# Ethernet.net
KiCad netlist of a schematic drawn in Altium Designer
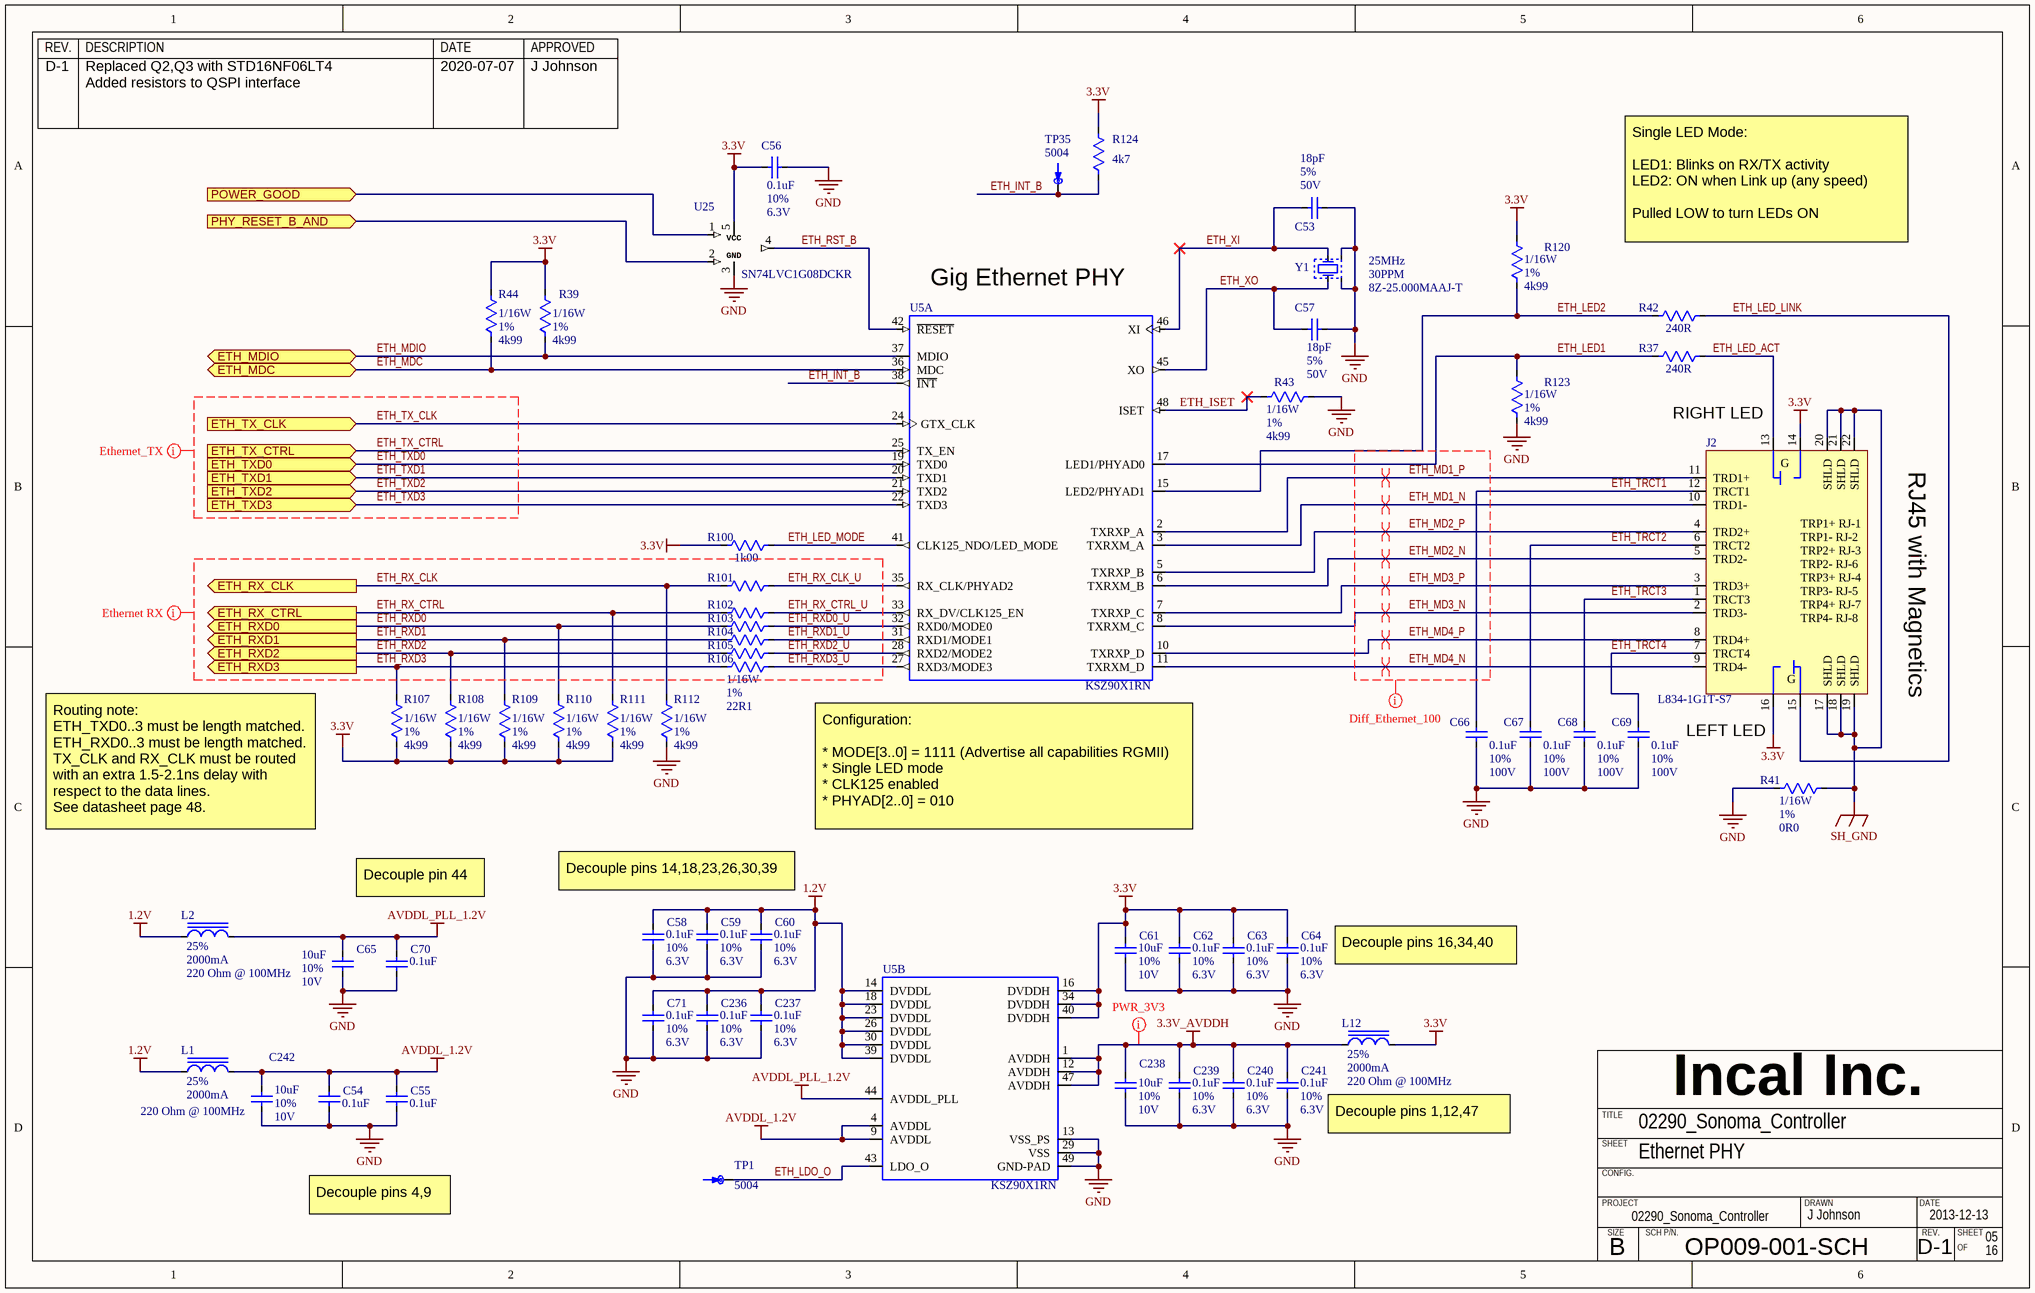
[diagram p0: Ethernet.SchDoc]

(export (version "E")
  (design (tool "Eeschema 10.0.6"))
  (components
    (comp (ref "C53")
      (value "18pF")
      (footprint "CAPC1005X33N")
      (description "Capacitor ceramic, C0G (NP0), 18pF, 50V, 5%, -55 to +125 C, EIA0402")
      (fields
        (field (name "TOLERANCE") "5%")
        (field (name "VOLTAGE") "50V")
        (field (name "Comment") "CAPACITOR_NP_TYPE1")
      )
      (libsource (lib "parts") (part "CAPACITOR_NP_TYPE1"))
    )
    (comp (ref "C54")
      (value "0.1uF")
      (footprint "CAPC0603X33N")
      (description "Capacitor ceramic, X5R, 0.1uF, 6.3V, 10%, -55 to +125 C, EIA0201")
      (fields (field (name "TOLERANCE") "10%") (field (name "VOLTAGE") "6.3V"))
      (libsource (lib "parts") (part "CAPACITOR_NP_TYPE1"))
    )
    (comp (ref "C55")
      (value "0.1uF")
      (footprint "CAPC0603X33N")
      (description "Capacitor ceramic, X5R, 0.1uF, 6.3V, 10%, -55 to +125 C, EIA0201")
      (fields (field (name "TOLERANCE") "10%") (field (name "VOLTAGE") "6.3V"))
      (libsource (lib "parts") (part "CAPACITOR_NP_TYPE1"))
    )
    (comp (ref "C56")
      (value "0.1uF")
      (footprint "CAPC0603X33N")
      (description "Capacitor ceramic, X5R, 0.1uF, 6.3V, 10%, -55 to +125 C, EIA0201")
      (fields
        (field (name "TOLERANCE") "10%")
        (field (name "VOLTAGE") "6.3V")
        (field (name "Comment") "CAPACITOR_NP_TYPE1")
      )
      (libsource (lib "parts") (part "CAPACITOR_NP_TYPE1"))
    )
    (comp (ref "C57")
      (value "18pF")
      (footprint "CAPC1005X33N")
      (description "Capacitor ceramic, C0G (NP0), 18pF, 50V, 5%, -55 to +125 C, EIA0402")
      (fields
        (field (name "TOLERANCE") "5%")
        (field (name "VOLTAGE") "50V")
        (field (name "Comment") "CAPACITOR_NP_TYPE1")
      )
      (libsource (lib "parts") (part "CAPACITOR_NP_TYPE1"))
    )
    (comp (ref "C58")
      (value "0.1uF")
      (footprint "CAPC0603X33N")
      (description "Capacitor ceramic, X5R, 0.1uF, 6.3V, 10%, -55 to +125 C, EIA0201")
      (fields
        (field (name "TOLERANCE") "10%")
        (field (name "VOLTAGE") "6.3V")
        (field (name "Comment") "CAPACITOR_NP_TYPE1")
      )
      (libsource (lib "parts") (part "CAPACITOR_NP_TYPE1"))
    )
    (comp (ref "C59")
      (value "0.1uF")
      (footprint "CAPC0603X33N")
      (description "Capacitor ceramic, X5R, 0.1uF, 6.3V, 10%, -55 to +125 C, EIA0201")
      (fields
        (field (name "TOLERANCE") "10%")
        (field (name "VOLTAGE") "6.3V")
        (field (name "Comment") "CAPACITOR_NP_TYPE1")
      )
      (libsource (lib "parts") (part "CAPACITOR_NP_TYPE1"))
    )
    (comp (ref "C60")
      (value "0.1uF")
      (footprint "CAPC0603X33N")
      (description "Capacitor ceramic, X5R, 0.1uF, 6.3V, 10%, -55 to +125 C, EIA0201")
      (fields
        (field (name "TOLERANCE") "10%")
        (field (name "VOLTAGE") "6.3V")
        (field (name "Comment") "CAPACITOR_NP_TYPE1")
      )
      (libsource (lib "parts") (part "CAPACITOR_NP_TYPE1"))
    )
    (comp (ref "C61")
      (value "10uF")
      (footprint "CAPC1608X38N")
      (description "Capacitor ceramic, X5R, 10uF, 10V, 10%, -55 to +85 C, EIA0603")
      (fields
        (field (name "TOLERANCE") "10%")
        (field (name "VOLTAGE") "10V")
        (field (name "Comment") "CAPACITOR_NP_TYPE1")
      )
      (libsource (lib "parts") (part "CAPACITOR_NP_TYPE1"))
    )
    (comp (ref "C62")
      (value "0.1uF")
      (footprint "CAPC0603X33N")
      (description "Capacitor ceramic, X5R, 0.1uF, 6.3V, 10%, -55 to +125 C, EIA0201")
      (fields
        (field (name "TOLERANCE") "10%")
        (field (name "VOLTAGE") "6.3V")
        (field (name "Comment") "CAPACITOR_NP_TYPE1")
      )
      (libsource (lib "parts") (part "CAPACITOR_NP_TYPE1"))
    )
    (comp (ref "C63")
      (value "0.1uF")
      (footprint "CAPC0603X33N")
      (description "Capacitor ceramic, X5R, 0.1uF, 6.3V, 10%, -55 to +125 C, EIA0201")
      (fields
        (field (name "TOLERANCE") "10%")
        (field (name "VOLTAGE") "6.3V")
        (field (name "Comment") "CAPACITOR_NP_TYPE1")
      )
      (libsource (lib "parts") (part "CAPACITOR_NP_TYPE1"))
    )
    (comp (ref "C64")
      (value "0.1uF")
      (footprint "CAPC0603X33N")
      (description "Capacitor ceramic, X5R, 0.1uF, 6.3V, 10%, -55 to +125 C, EIA0201")
      (fields
        (field (name "TOLERANCE") "10%")
        (field (name "VOLTAGE") "6.3V")
        (field (name "Comment") "CAPACITOR_NP_TYPE1")
      )
      (libsource (lib "parts") (part "CAPACITOR_NP_TYPE1"))
    )
    (comp (ref "C65")
      (value "10uF")
      (footprint "CAPC1608X38N")
      (description "Capacitor ceramic, X5R, 10uF, 10V, 10%, -55 to +85 C, EIA0603")
      (fields
        (field (name "TOLERANCE") "10%")
        (field (name "VOLTAGE") "10V")
        (field (name "Comment") "CAPACITOR_NP_TYPE1")
      )
      (libsource (lib "parts") (part "CAPACITOR_NP_TYPE1"))
    )
    (comp (ref "C66")
      (value "0.1uF")
      (footprint "CAPC1608X38N")
      (description "Capacitor ceramic, X7R, 0.1uF, 100V, 10%, -55 to +125 C, EIA0603")
      (fields
        (field (name "TOLERANCE") "10%")
        (field (name "VOLTAGE") "100V")
        (field (name "Comment") "CAPACITOR_NP_TYPE1")
      )
      (libsource (lib "parts") (part "CAPACITOR_NP_TYPE1"))
    )
    (comp (ref "C67")
      (value "0.1uF")
      (footprint "CAPC1608X38N")
      (description "Capacitor ceramic, X7R, 0.1uF, 100V, 10%, -55 to +125 C, EIA0603")
      (fields
        (field (name "TOLERANCE") "10%")
        (field (name "VOLTAGE") "100V")
        (field (name "Comment") "CAPACITOR_NP_TYPE1")
      )
      (libsource (lib "parts") (part "CAPACITOR_NP_TYPE1"))
    )
    (comp (ref "C68")
      (value "0.1uF")
      (footprint "CAPC1608X38N")
      (description "Capacitor ceramic, X7R, 0.1uF, 100V, 10%, -55 to +125 C, EIA0603")
      (fields
        (field (name "TOLERANCE") "10%")
        (field (name "VOLTAGE") "100V")
        (field (name "Comment") "CAPACITOR_NP_TYPE1")
      )
      (libsource (lib "parts") (part "CAPACITOR_NP_TYPE1"))
    )
    (comp (ref "C69")
      (value "0.1uF")
      (footprint "CAPC1608X38N")
      (description "Capacitor ceramic, X7R, 0.1uF, 100V, 10%, -55 to +125 C, EIA0603")
      (fields
        (field (name "TOLERANCE") "10%")
        (field (name "VOLTAGE") "100V")
        (field (name "Comment") "CAPACITOR_NP_TYPE1")
      )
      (libsource (lib "parts") (part "CAPACITOR_NP_TYPE1"))
    )
    (comp (ref "C70")
      (value "0.1uF")
      (footprint "CAPC0603X33N")
      (description "Capacitor ceramic, X5R, 0.1uF, 6.3V, 10%, -55 to +125 C, EIA0201")
      (fields (field (name "TOLERANCE") "10%") (field (name "VOLTAGE") "6.3V"))
      (libsource (lib "parts") (part "CAPACITOR_NP_TYPE1"))
    )
    (comp (ref "C71")
      (value "0.1uF")
      (footprint "CAPC0603X33N")
      (description "Capacitor ceramic, X5R, 0.1uF, 6.3V, 10%, -55 to +125 C, EIA0201")
      (fields
        (field (name "TOLERANCE") "10%")
        (field (name "VOLTAGE") "6.3V")
        (field (name "Comment") "CAPACITOR_NP_TYPE1")
      )
      (libsource (lib "parts") (part "CAPACITOR_NP_TYPE1"))
    )
    (comp (ref "C236")
      (value "0.1uF")
      (footprint "CAPC0603X33N")
      (description "Capacitor ceramic, X5R, 0.1uF, 6.3V, 10%, -55 to +125 C, EIA0201")
      (fields
        (field (name "TOLERANCE") "10%")
        (field (name "VOLTAGE") "6.3V")
        (field (name "Comment") "CAPACITOR_NP_TYPE1")
      )
      (libsource (lib "parts") (part "CAPACITOR_NP_TYPE1"))
    )
    (comp (ref "C237")
      (value "0.1uF")
      (footprint "CAPC0603X33N")
      (description "Capacitor ceramic, X5R, 0.1uF, 6.3V, 10%, -55 to +125 C, EIA0201")
      (fields
        (field (name "TOLERANCE") "10%")
        (field (name "VOLTAGE") "6.3V")
        (field (name "Comment") "CAPACITOR_NP_TYPE1")
      )
      (libsource (lib "parts") (part "CAPACITOR_NP_TYPE1"))
    )
    (comp (ref "C238")
      (value "10uF")
      (footprint "CAPC1608X38N")
      (description "Capacitor ceramic, X5R, 10uF, 10V, 10%, -55 to +85 C, EIA0603")
      (fields
        (field (name "TOLERANCE") "10%")
        (field (name "VOLTAGE") "10V")
        (field (name "Comment") "CAPACITOR_NP_TYPE1")
      )
      (libsource (lib "parts") (part "CAPACITOR_NP_TYPE1"))
    )
    (comp (ref "C239")
      (value "0.1uF")
      (footprint "CAPC0603X33N")
      (description "Capacitor ceramic, X5R, 0.1uF, 6.3V, 10%, -55 to +125 C, EIA0201")
      (fields
        (field (name "TOLERANCE") "10%")
        (field (name "VOLTAGE") "6.3V")
        (field (name "Comment") "CAPACITOR_NP_TYPE1")
      )
      (libsource (lib "parts") (part "CAPACITOR_NP_TYPE1"))
    )
    (comp (ref "C240")
      (value "0.1uF")
      (footprint "CAPC0603X33N")
      (description "Capacitor ceramic, X5R, 0.1uF, 6.3V, 10%, -55 to +125 C, EIA0201")
      (fields
        (field (name "TOLERANCE") "10%")
        (field (name "VOLTAGE") "6.3V")
        (field (name "Comment") "CAPACITOR_NP_TYPE1")
      )
      (libsource (lib "parts") (part "CAPACITOR_NP_TYPE1"))
    )
    (comp (ref "C241")
      (value "0.1uF")
      (footprint "CAPC0603X33N")
      (description "Capacitor ceramic, X5R, 0.1uF, 6.3V, 10%, -55 to +125 C, EIA0201")
      (fields
        (field (name "TOLERANCE") "10%")
        (field (name "VOLTAGE") "6.3V")
        (field (name "Comment") "CAPACITOR_NP_TYPE1")
      )
      (libsource (lib "parts") (part "CAPACITOR_NP_TYPE1"))
    )
    (comp (ref "C242")
      (value "10uF")
      (footprint "CAPC1608X38N")
      (description "Capacitor ceramic, X5R, 10uF, 10V, 10%, -55 to +85 C, EIA0603")
      (fields
        (field (name "TOLERANCE") "10%")
        (field (name "VOLTAGE") "10V")
        (field (name "Comment") "CAPACITOR_NP_TYPE1")
      )
      (libsource (lib "parts") (part "CAPACITOR_NP_TYPE1"))
    )
    (comp (ref "J2")
      (value "L834-1G1T-S7")
      (footprint "L834-1G1T-S7")
      (description "Connector RJ45, 10/100/1000, with Mag & 2 LED G/G, Tab down")
      (fields (field (name "Comment") "CON_RJ45_MAG_TYPE_9"))
      (libsource (lib "parts") (part "CON_RJ45_MAG_TYPE_9"))
    )
    (comp (ref "L1")
      (value "220 Ohm @ 100MHz")
      (footprint "INDC2012X85N")
      (description "Ferrite chip, 220 Ohm @ 100MHz, 2000mA, 25%, -55 to +125 C, 0805")
      (fields
        (field (name "TOLERANCE") "25%")
        (field (name "CURRENT") "2000mA")
        (field (name "Comment") "INDUCTOR_CORE_TYPE1")
      )
      (libsource (lib "parts") (part "INDUCTOR_CORE_TYPE1"))
    )
    (comp (ref "L2")
      (value "220 Ohm @ 100MHz")
      (footprint "INDC2012X85N")
      (description "Ferrite chip, 220 Ohm @ 100MHz, 2000mA, 25%, -55 to +125 C, 0805")
      (fields
        (field (name "TOLERANCE") "25%")
        (field (name "CURRENT") "2000mA")
        (field (name "Comment") "INDUCTOR_CORE_TYPE1")
      )
      (libsource (lib "parts") (part "INDUCTOR_CORE_TYPE1"))
    )
    (comp (ref "L12")
      (value "220 Ohm @ 100MHz")
      (footprint "INDC2012X85N")
      (description "Ferrite chip, 220 Ohm @ 100MHz, 2000mA, 25%, -55 to +125 C, 0805")
      (fields
        (field (name "TOLERANCE") "25%")
        (field (name "CURRENT") "2000mA")
        (field (name "Comment") "INDUCTOR_CORE_TYPE1")
      )
      (libsource (lib "parts") (part "INDUCTOR_CORE_TYPE1"))
    )
    (comp (ref "R37")
      (value "240R")
      (footprint "RESC1005X33N")
      (description "Resistor, 240R, 1/16W, 1%, -50 to +155 C, EIA0402, EIA(M)1005")
      (fields (field (name "VOLTAGE") "50V") (field (name "POWER") "1/16W"))
      (libsource (lib "parts") (part "RESISTOR_TYPE1"))
    )
    (comp (ref "R39")
      (value "4k99")
      (footprint "RESC1005X33N")
      (description "Resistor, 4k99, 1/16W, 1%, -50 to +155 C, EIA0402, EIA(M)1005")
      (fields (field (name "VOLTAGE") "50V") (field (name "POWER") "1/16W") (field (name "TOLERANCE") "1%"))
      (libsource (lib "parts") (part "RESISTOR_TYPE1"))
    )
    (comp (ref "R41")
      (value "0R0")
      (footprint "RESC1005X33N")
      (description "Resistor, 0R0, 1/16W, 1%, -50 to +155 C, EIA0402, EIA(M)1005")
      (fields (field (name "VOLTAGE") "50V") (field (name "POWER") "1/16W") (field (name "TOLERANCE") "1%"))
      (libsource (lib "parts") (part "RESISTOR_TYPE1"))
    )
    (comp (ref "R42")
      (value "240R")
      (footprint "RESC1005X33N")
      (description "Resistor, 240R, 1/16W, 1%, -50 to +155 C, EIA0402, EIA(M)1005")
      (fields (field (name "VOLTAGE") "50V") (field (name "POWER") "1/16W"))
      (libsource (lib "parts") (part "RESISTOR_TYPE1"))
    )
    (comp (ref "R43")
      (value "4k99")
      (footprint "RESC1005X33N")
      (description "Resistor, 4k99, 1/16W, 1%, -50 to +155 C, EIA0402, EIA(M)1005")
      (fields (field (name "VOLTAGE") "50V") (field (name "POWER") "1/16W") (field (name "TOLERANCE") "1%"))
      (libsource (lib "parts") (part "RESISTOR_TYPE1"))
    )
    (comp (ref "R44")
      (value "4k99")
      (footprint "RESC1005X33N")
      (description "Resistor, 4k99, 1/16W, 1%, -50 to +155 C, EIA0402, EIA(M)1005")
      (fields (field (name "VOLTAGE") "50V") (field (name "POWER") "1/16W") (field (name "TOLERANCE") "1%"))
      (libsource (lib "parts") (part "RESISTOR_TYPE1"))
    )
    (comp (ref "R100")
      (value "1k00")
      (footprint "RESC1005X33N")
      (description "Resistor, 1k00, 1/16W, 1%, -55 to +155 C, EIA0402")
      (fields (field (name "VOLTAGE") "50V") (field (name "POWER") "1/16W"))
      (libsource (lib "parts") (part "RESISTOR_TYPE1"))
    )
    (comp (ref "R101")
      (value "*")
      (footprint "RESC1005X33N")
      (description "Resistor, 22R1, 1/16W, 1%, -55 to +155 C, EIA0402")
      (fields (field (name "VOLTAGE") "50V") (field (name "POWER") "1/16W"))
      (libsource (lib "parts") (part "RESISTOR_TYPE1"))
    )
    (comp (ref "R102")
      (value "*")
      (footprint "RESC1005X33N")
      (description "Resistor, 22R1, 1/16W, 1%, -55 to +155 C, EIA0402")
      (fields (field (name "VOLTAGE") "50V") (field (name "POWER") "1/16W"))
      (libsource (lib "parts") (part "RESISTOR_TYPE1"))
    )
    (comp (ref "R103")
      (value "*")
      (footprint "RESC1005X33N")
      (description "Resistor, 22R1, 1/16W, 1%, -55 to +155 C, EIA0402")
      (fields (field (name "VOLTAGE") "50V") (field (name "POWER") "1/16W"))
      (libsource (lib "parts") (part "RESISTOR_TYPE1"))
    )
    (comp (ref "R104")
      (value "*")
      (footprint "RESC1005X33N")
      (description "Resistor, 22R1, 1/16W, 1%, -55 to +155 C, EIA0402")
      (fields (field (name "VOLTAGE") "50V") (field (name "POWER") "1/16W"))
      (libsource (lib "parts") (part "RESISTOR_TYPE1"))
    )
    (comp (ref "R105")
      (value "*")
      (footprint "RESC1005X33N")
      (description "Resistor, 22R1, 1/16W, 1%, -55 to +155 C, EIA0402")
      (fields (field (name "VOLTAGE") "50V") (field (name "POWER") "1/16W"))
      (libsource (lib "parts") (part "RESISTOR_TYPE1"))
    )
    (comp (ref "R106")
      (value "22R1")
      (footprint "RESC1005X33N")
      (description "Resistor, 22R1, 1/16W, 1%, -55 to +155 C, EIA0402")
      (fields (field (name "VOLTAGE") "50V") (field (name "POWER") "1/16W") (field (name "TOLERANCE") "1%"))
      (libsource (lib "parts") (part "RESISTOR_TYPE1"))
    )
    (comp (ref "R107")
      (value "4k99")
      (footprint "RESC1005X33N")
      (description "Resistor, 4k99, 1/16W, 1%, -50 to +155 C, EIA0402, EIA(M)1005")
      (fields (field (name "VOLTAGE") "50V") (field (name "POWER") "1/16W") (field (name "TOLERANCE") "1%"))
      (libsource (lib "parts") (part "RESISTOR_TYPE1"))
    )
    (comp (ref "R108")
      (value "4k99")
      (footprint "RESC1005X33N")
      (description "Resistor, 4k99, 1/16W, 1%, -50 to +155 C, EIA0402, EIA(M)1005")
      (fields (field (name "VOLTAGE") "50V") (field (name "POWER") "1/16W") (field (name "TOLERANCE") "1%"))
      (libsource (lib "parts") (part "RESISTOR_TYPE1"))
    )
    (comp (ref "R109")
      (value "4k99")
      (footprint "RESC1005X33N")
      (description "Resistor, 4k99, 1/16W, 1%, -50 to +155 C, EIA0402, EIA(M)1005")
      (fields (field (name "VOLTAGE") "50V") (field (name "POWER") "1/16W") (field (name "TOLERANCE") "1%"))
      (libsource (lib "parts") (part "RESISTOR_TYPE1"))
    )
    (comp (ref "R110")
      (value "4k99")
      (footprint "RESC1005X33N")
      (description "Resistor, 4k99, 1/16W, 1%, -50 to +155 C, EIA0402, EIA(M)1005")
      (fields (field (name "VOLTAGE") "50V") (field (name "POWER") "1/16W") (field (name "TOLERANCE") "1%"))
      (libsource (lib "parts") (part "RESISTOR_TYPE1"))
    )
    (comp (ref "R111")
      (value "4k99")
      (footprint "RESC1005X33N")
      (description "Resistor, 4k99, 1/16W, 1%, -50 to +155 C, EIA0402, EIA(M)1005")
      (fields (field (name "VOLTAGE") "50V") (field (name "POWER") "1/16W") (field (name "TOLERANCE") "1%"))
      (libsource (lib "parts") (part "RESISTOR_TYPE1"))
    )
    (comp (ref "R112")
      (value "4k99")
      (footprint "RESC1005X33N")
      (description "Resistor, 4k99, 1/16W, 1%, -50 to +155 C, EIA0402, EIA(M)1005")
      (fields (field (name "VOLTAGE") "50V") (field (name "POWER") "1/16W") (field (name "TOLERANCE") "1%"))
      (libsource (lib "parts") (part "RESISTOR_TYPE1"))
    )
    (comp (ref "R120")
      (value "4k99")
      (footprint "RESC1005X33N")
      (description "Resistor, 4k99, 1/16W, 1%, -50 to +155 C, EIA0402, EIA(M)1005")
      (fields (field (name "VOLTAGE") "50V") (field (name "POWER") "1/16W") (field (name "TOLERANCE") "1%"))
      (libsource (lib "parts") (part "RESISTOR_TYPE1"))
    )
    (comp (ref "R123")
      (value "4k99")
      (footprint "RESC1005X33N")
      (description "Resistor, 4k99, 1/16W, 1%, -50 to +155 C, EIA0402, EIA(M)1005")
      (fields (field (name "VOLTAGE") "50V") (field (name "POWER") "1/16W") (field (name "TOLERANCE") "1%"))
      (libsource (lib "parts") (part "RESISTOR_TYPE1"))
    )
    (comp (ref "R124")
      (value "4k7")
      (footprint "RESC1005X33N")
      (description "Resistor, 4k7, 1/16W, 1%, -55 to +155 C, EIA0402")
      (fields (field (name "VOLTAGE") "50V") (field (name "POWER") "1/16W"))
      (libsource (lib "parts") (part "RESISTOR_TYPE1"))
    )
    (comp (ref "TP1")
      (value "5004")
      (footprint "KEY_5004")
      (description "Test point bead, yellow, Keystone Electronics, Thru-hole,")
      (fields (field (name "POWER") "Pow") (field (name "VOLTAGE") "Vol"))
      (libsource (lib "") (part "TEST_POINT_TYPE4_1"))
    )
    (comp (ref "TP35")
      (value "5004")
      (footprint "KEY_5004")
      (description "Test point bead, yellow, Keystone Electronics, Thru-hole,")
      (fields (field (name "POWER") "Pow") (field (name "VOLTAGE") "Vol"))
      (libsource (lib "parts") (part "TEST_POINT_TYPE4"))
    )
    (comp (ref "U5")
      (value "KSZ90X1RN")
      (footprint "QFN50P700X700X90-49N")
      (description "10/100/1000 ethernet PHY with RGMII, 3.3V,1.2V, 0, -40 to +85 C, 0, QFN48")
      (fields (field (name "POWER") "0") (field (name "VOLTAGE") "3.3V,1.2V"))
      (libsource (lib "parts") (part "KSZ90X1RN"))
    )
    (comp (ref "U25")
      (value "SN74LVC1G08DCKR")
      (footprint "SOT65P210X110-5N")
      (description "Single 2-input AND gate, 1.65V to 5.5V")
      (fields (field (name "POWER") "Pow") (field (name "VOLTAGE") "1.65V to 5.5V"))
      (libsource (lib "parts") (part "SN74LVC1G08"))
    )
    (comp (ref "Y1")
      (value "25MHz")
      (footprint "OSCSC185P200X250X55-4N")
      (description "Crystal, 25MHz, 30ppm, 100uW, -40 to +85 C, SMT")
      (fields
        (field (name "POWER") "100uW")
        (field (name "TOLERANCE") "30PPM")
        (field (name "MFG PART NUMBER 1") "8Z-25.000MAAJ-T")
      )
      (libsource (lib "parts") (part "XTAL_TYPE3"))
    )
  )
  (nets
    (net (code "1") (name "/ETH_INT_B") (class "Default")
      (node (ref "R124") (pin "2") (pinfunction "2_2") (pintype "passive"))
      (node (ref "TP35") (pin "1") (pinfunction "1_1") (pintype "passive"))
      (node (ref "U5") (pin "38") (pinfunction "~{INT}_38") (pintype "output"))
    )
    (net (code "2") (name "/ETH_ISET") (class "Default")
      (node (ref "R43") (pin "2") (pinfunction "2_2") (pintype "passive"))
      (node (ref "U5") (pin "48") (pinfunction "ISET_48") (pintype "input"))
    )
    (net (code "3") (name "/ETH_LDO_O") (class "Default")
      (node (ref "TP1") (pin "1") (pinfunction "1_1") (pintype "passive"))
      (node (ref "U5") (pin "43") (pinfunction "LDO_O_43") (pintype "power_in"))
    )
    (net (code "4") (name "/ETH_LED1") (class "Default")
      (node (ref "R123") (pin "2") (pinfunction "2_2") (pintype "passive"))
      (node (ref "R37") (pin "1") (pinfunction "1_1") (pintype "passive"))
      (node (ref "U5") (pin "17") (pinfunction "LED1/PHYAD0_17") (pintype "bidirectional"))
    )
    (net (code "5") (name "/ETH_LED2") (class "Default")
      (node (ref "R120") (pin "1") (pinfunction "1_1") (pintype "passive"))
      (node (ref "R42") (pin "1") (pinfunction "1_1") (pintype "passive"))
      (node (ref "U5") (pin "15") (pinfunction "LED2/PHYAD1_15") (pintype "bidirectional"))
    )
    (net (code "6") (name "/ETH_LED_ACT") (class "Default")
      (node (ref "J2") (pin "13") (pinfunction "K2_13") (pintype "passive"))
      (node (ref "R37") (pin "2") (pinfunction "2_2") (pintype "passive"))
    )
    (net (code "7") (name "/ETH_LED_LINK") (class "Default")
      (node (ref "J2") (pin "15") (pinfunction "18_15") (pintype "passive"))
      (node (ref "R42") (pin "2") (pinfunction "2_2") (pintype "passive"))
    )
    (net (code "8") (name "/ETH_LED_MODE") (class "Default")
      (node (ref "R100") (pin "2") (pinfunction "2_2") (pintype "passive"))
      (node (ref "U5") (pin "41") (pinfunction "CLK125_NDO/LED_MODE_41") (pintype "output"))
    )
    (net (code "9") (name "/ETH_MD1_N") (class "Default")
      (node (ref "J2") (pin "10") (pinfunction "TRD1-_10") (pintype "bidirectional"))
      (node (ref "U5") (pin "3") (pinfunction "TXRXM_A_3") (pintype "bidirectional"))
    )
    (net (code "10") (name "/ETH_MD1_P") (class "Default")
      (node (ref "J2") (pin "11") (pinfunction "TRD1+_11") (pintype "bidirectional"))
      (node (ref "U5") (pin "2") (pinfunction "TXRXP_A_2") (pintype "bidirectional"))
    )
    (net (code "11") (name "/ETH_MD2_N") (class "Default")
      (node (ref "J2") (pin "5") (pinfunction "TRD2-_5") (pintype "bidirectional"))
      (node (ref "U5") (pin "6") (pinfunction "TXRXM_B_6") (pintype "bidirectional"))
    )
    (net (code "12") (name "/ETH_MD2_P") (class "Default")
      (node (ref "J2") (pin "4") (pinfunction "TRD2+_4") (pintype "bidirectional"))
      (node (ref "U5") (pin "5") (pinfunction "TXRXP_B_5") (pintype "bidirectional"))
    )
    (net (code "13") (name "/ETH_MD3_N") (class "Default")
      (node (ref "J2") (pin "2") (pinfunction "TRD3-_2") (pintype "bidirectional"))
      (node (ref "U5") (pin "8") (pinfunction "TXRXM_C_8") (pintype "bidirectional"))
    )
    (net (code "14") (name "/ETH_MD3_P") (class "Default")
      (node (ref "J2") (pin "3") (pinfunction "TRD3+_3") (pintype "bidirectional"))
      (node (ref "U5") (pin "7") (pinfunction "TXRXP_C_7") (pintype "bidirectional"))
    )
    (net (code "15") (name "/ETH_MD4_N") (class "Default")
      (node (ref "J2") (pin "9") (pinfunction "TRD4-_9") (pintype "bidirectional"))
      (node (ref "U5") (pin "11") (pinfunction "TXRXM_D_11") (pintype "bidirectional"))
    )
    (net (code "16") (name "/ETH_MD4_P") (class "Default")
      (node (ref "J2") (pin "8") (pinfunction "TRD4+_8") (pintype "bidirectional"))
      (node (ref "U5") (pin "10") (pinfunction "TXRXP_D_10") (pintype "bidirectional"))
    )
    (net (code "17") (name "/ETH_MDC") (class "Default")
      (node (ref "R44") (pin "1") (pinfunction "1_1") (pintype "passive"))
      (node (ref "U5") (pin "36") (pinfunction "MDC_36") (pintype "input"))
    )
    (net (code "18") (name "/ETH_MDIO") (class "Default")
      (node (ref "R39") (pin "1") (pinfunction "1_1") (pintype "passive"))
      (node (ref "U5") (pin "37") (pinfunction "MDIO_37") (pintype "bidirectional"))
    )
    (net (code "19") (name "/ETH_RST_B") (class "Default")
      (node (ref "U25") (pin "4") (pinfunction "Y_4") (pintype "output"))
      (node (ref "U5") (pin "42") (pinfunction "~{RESET}_42") (pintype "input"))
    )
    (net (code "20") (name "/ETH_RXD0") (class "Default")
      (node (ref "R103") (pin "1") (pinfunction "1_1") (pintype "passive"))
      (node (ref "R110") (pin "2") (pinfunction "2_2") (pintype "passive"))
    )
    (net (code "21") (name "/ETH_RXD0_U") (class "Default")
      (node (ref "R103") (pin "2") (pinfunction "2_2") (pintype "passive"))
      (node (ref "U5") (pin "32") (pinfunction "RXD0/MODE0_32") (pintype "output"))
    )
    (net (code "22") (name "/ETH_RXD1") (class "Default")
      (node (ref "R104") (pin "1") (pinfunction "1_1") (pintype "passive"))
      (node (ref "R109") (pin "2") (pinfunction "2_2") (pintype "passive"))
    )
    (net (code "23") (name "/ETH_RXD1_U") (class "Default")
      (node (ref "R104") (pin "2") (pinfunction "2_2") (pintype "passive"))
      (node (ref "U5") (pin "31") (pinfunction "RXD1/MODE1_31") (pintype "output"))
    )
    (net (code "24") (name "/ETH_RXD2") (class "Default")
      (node (ref "R105") (pin "1") (pinfunction "1_1") (pintype "passive"))
      (node (ref "R108") (pin "2") (pinfunction "2_2") (pintype "passive"))
    )
    (net (code "25") (name "/ETH_RXD2_U") (class "Default")
      (node (ref "R105") (pin "2") (pinfunction "2_2") (pintype "passive"))
      (node (ref "U5") (pin "28") (pinfunction "RXD2/MODE2_28") (pintype "output"))
    )
    (net (code "26") (name "/ETH_RXD3") (class "Default")
      (node (ref "R106") (pin "1") (pinfunction "1_1") (pintype "passive"))
      (node (ref "R107") (pin "2") (pinfunction "2_2") (pintype "passive"))
    )
    (net (code "27") (name "/ETH_RXD3_U") (class "Default")
      (node (ref "R106") (pin "2") (pinfunction "2_2") (pintype "passive"))
      (node (ref "U5") (pin "27") (pinfunction "RXD3/MODE3_27") (pintype "output"))
    )
    (net (code "28") (name "/ETH_RX_CLK") (class "Default")
      (node (ref "R101") (pin "1") (pinfunction "1_1") (pintype "passive"))
      (node (ref "R112") (pin "2") (pinfunction "2_2") (pintype "passive"))
    )
    (net (code "29") (name "/ETH_RX_CLK_U") (class "Default")
      (node (ref "R101") (pin "2") (pinfunction "2_2") (pintype "passive"))
      (node (ref "U5") (pin "35") (pinfunction "RX_CLK/PHYAD2_35") (pintype "output"))
    )
    (net (code "30") (name "/ETH_RX_CTRL") (class "Default")
      (node (ref "R102") (pin "1") (pinfunction "1_1") (pintype "passive"))
      (node (ref "R111") (pin "2") (pinfunction "2_2") (pintype "passive"))
    )
    (net (code "31") (name "/ETH_RX_CTRL_U") (class "Default")
      (node (ref "R102") (pin "2") (pinfunction "2_2") (pintype "passive"))
      (node (ref "U5") (pin "33") (pinfunction "RX_DV/CLK125_EN_33") (pintype "output"))
    )
    (net (code "32") (name "/ETH_TRCT1") (class "Default")
      (node (ref "C66") (pin "1") (pinfunction "1_1") (pintype "passive"))
      (node (ref "J2") (pin "12") (pinfunction "TRCT1_12") (pintype "passive"))
    )
    (net (code "33") (name "/ETH_TRCT2") (class "Default")
      (node (ref "C67") (pin "1") (pinfunction "1_1") (pintype "passive"))
      (node (ref "J2") (pin "6") (pinfunction "TRCT2_6") (pintype "passive"))
    )
    (net (code "34") (name "/ETH_TRCT3") (class "Default")
      (node (ref "C68") (pin "1") (pinfunction "1_1") (pintype "passive"))
      (node (ref "J2") (pin "1") (pinfunction "TRCT3_1") (pintype "passive"))
    )
    (net (code "35") (name "/ETH_TRCT4") (class "Default")
      (node (ref "C69") (pin "1") (pinfunction "1_1") (pintype "passive"))
      (node (ref "J2") (pin "7") (pinfunction "TRCT4_7") (pintype "passive"))
    )
    (net (code "36") (name "/ETH_TXD0") (class "Default")
      (node (ref "U5") (pin "19") (pinfunction "TXD0_19") (pintype "input"))
    )
    (net (code "37") (name "/ETH_TXD1") (class "Default")
      (node (ref "U5") (pin "20") (pinfunction "TXD1_20") (pintype "input"))
    )
    (net (code "38") (name "/ETH_TXD2") (class "Default")
      (node (ref "U5") (pin "21") (pinfunction "TXD2_21") (pintype "input"))
    )
    (net (code "39") (name "/ETH_TXD3") (class "Default")
      (node (ref "U5") (pin "22") (pinfunction "TXD3_22") (pintype "input"))
    )
    (net (code "40") (name "/ETH_TX_CLK") (class "Default")
      (node (ref "U5") (pin "24") (pinfunction "GTX_CLK_24") (pintype "input"))
    )
    (net (code "41") (name "/ETH_TX_CTRL") (class "Default")
      (node (ref "U5") (pin "25") (pinfunction "TX_EN_25") (pintype "input"))
    )
    (net (code "42") (name "/ETH_XI") (class "Default")
      (node (ref "C53") (pin "1") (pinfunction "1_1") (pintype "passive"))
      (node (ref "U5") (pin "46") (pinfunction "XI_46") (pintype "input"))
      (node (ref "Y1") (pin "3") (pinfunction "3_3") (pintype "passive"))
    )
    (net (code "43") (name "/ETH_XO") (class "Default")
      (node (ref "C57") (pin "1") (pinfunction "1_1") (pintype "passive"))
      (node (ref "U5") (pin "45") (pinfunction "XO_45") (pintype "output"))
      (node (ref "Y1") (pin "1") (pinfunction "1_1") (pintype "passive"))
    )
    (net (code "44") (name "/PHY_RESET_B_AND") (class "Default")
      (node (ref "U25") (pin "2") (pinfunction "B_2") (pintype "input"))
    )
    (net (code "45") (name "/POWER_GOOD") (class "Default")
      (node (ref "U25") (pin "1") (pinfunction "A_1") (pintype "input"))
    )
    (net (code "46") (name "1.2V") (class "Default")
      (node (ref "C236") (pin "1") (pinfunction "1_1") (pintype "passive"))
      (node (ref "C237") (pin "1") (pinfunction "1_1") (pintype "passive"))
      (node (ref "C58") (pin "1") (pinfunction "1_1") (pintype "passive"))
      (node (ref "C59") (pin "1") (pinfunction "1_1") (pintype "passive"))
      (node (ref "C60") (pin "1") (pinfunction "1_1") (pintype "passive"))
      (node (ref "C71") (pin "1") (pinfunction "1_1") (pintype "passive"))
      (node (ref "L1") (pin "1") (pinfunction "1_1") (pintype "passive"))
      (node (ref "L2") (pin "1") (pinfunction "1_1") (pintype "passive"))
      (node (ref "U5") (pin "14") (pinfunction "DVDDL_14") (pintype "power_in"))
      (node (ref "U5") (pin "18") (pinfunction "DVDDL_18") (pintype "power_in"))
      (node (ref "U5") (pin "23") (pinfunction "DVDDL_23") (pintype "power_in"))
      (node (ref "U5") (pin "26") (pinfunction "DVDDL_26") (pintype "power_in"))
      (node (ref "U5") (pin "30") (pinfunction "DVDDL_30") (pintype "power_in"))
      (node (ref "U5") (pin "39") (pinfunction "DVDDL_39") (pintype "power_in"))
    )
    (net (code "47") (name "3.3V") (class "Default")
      (node (ref "C56") (pin "1") (pinfunction "1_1") (pintype "passive"))
      (node (ref "C61") (pin "1") (pinfunction "1_1") (pintype "passive"))
      (node (ref "C62") (pin "1") (pinfunction "1_1") (pintype "passive"))
      (node (ref "C63") (pin "1") (pinfunction "1_1") (pintype "passive"))
      (node (ref "C64") (pin "1") (pinfunction "1_1") (pintype "passive"))
      (node (ref "J2") (pin "14") (pinfunction "A2_14") (pintype "passive"))
      (node (ref "J2") (pin "16") (pinfunction "A1_16") (pintype "passive"))
      (node (ref "L12") (pin "2") (pinfunction "2_2") (pintype "passive"))
      (node (ref "R100") (pin "1") (pinfunction "1_1") (pintype "passive"))
      (node (ref "R107") (pin "1") (pinfunction "1_1") (pintype "passive"))
      (node (ref "R108") (pin "1") (pinfunction "1_1") (pintype "passive"))
      (node (ref "R109") (pin "1") (pinfunction "1_1") (pintype "passive"))
      (node (ref "R110") (pin "1") (pinfunction "1_1") (pintype "passive"))
      (node (ref "R111") (pin "1") (pinfunction "1_1") (pintype "passive"))
      (node (ref "R120") (pin "2") (pinfunction "2_2") (pintype "passive"))
      (node (ref "R124") (pin "1") (pinfunction "1_1") (pintype "passive"))
      (node (ref "R39") (pin "2") (pinfunction "2_2") (pintype "passive"))
      (node (ref "R44") (pin "2") (pinfunction "2_2") (pintype "passive"))
      (node (ref "U25") (pin "5") (pinfunction "VCC_5") (pintype "power_in"))
      (node (ref "U5") (pin "16") (pinfunction "DVDDH_16") (pintype "power_in"))
      (node (ref "U5") (pin "34") (pinfunction "DVDDH_34") (pintype "power_in"))
      (node (ref "U5") (pin "40") (pinfunction "DVDDH_40") (pintype "power_in"))
    )
    (net (code "48") (name "3.3V_AVDDH") (class "Default")
      (node (ref "C238") (pin "1") (pinfunction "1_1") (pintype "passive"))
      (node (ref "C239") (pin "1") (pinfunction "1_1") (pintype "passive"))
      (node (ref "C240") (pin "1") (pinfunction "1_1") (pintype "passive"))
      (node (ref "C241") (pin "1") (pinfunction "1_1") (pintype "passive"))
      (node (ref "L12") (pin "1") (pinfunction "1_1") (pintype "passive"))
      (node (ref "U5") (pin "1") (pinfunction "AVDDH_1") (pintype "power_in"))
      (node (ref "U5") (pin "12") (pinfunction "AVDDH_12") (pintype "power_in"))
      (node (ref "U5") (pin "47") (pinfunction "AVDDH_47") (pintype "power_in"))
    )
    (net (code "49") (name "AVDDL_1.2V") (class "Default")
      (node (ref "C242") (pin "1") (pinfunction "1_1") (pintype "passive"))
      (node (ref "C54") (pin "1") (pinfunction "1_1") (pintype "passive"))
      (node (ref "C55") (pin "1") (pinfunction "1_1") (pintype "passive"))
      (node (ref "L1") (pin "2") (pinfunction "2_2") (pintype "passive"))
      (node (ref "U5") (pin "4") (pinfunction "AVDDL_4") (pintype "power_in"))
      (node (ref "U5") (pin "9") (pinfunction "AVDDL_9") (pintype "power_in"))
    )
    (net (code "50") (name "AVDDL_PLL_1.2V") (class "Default")
      (node (ref "C65") (pin "1") (pinfunction "1_1") (pintype "passive"))
      (node (ref "C70") (pin "1") (pinfunction "1_1") (pintype "passive"))
      (node (ref "L2") (pin "2") (pinfunction "2_2") (pintype "passive"))
      (node (ref "U5") (pin "44") (pinfunction "AVDDL_PLL_44") (pintype "power_in"))
    )
    (net (code "51") (name "GND") (class "Default")
      (node (ref "C236") (pin "2") (pinfunction "2_2") (pintype "passive"))
      (node (ref "C237") (pin "2") (pinfunction "2_2") (pintype "passive"))
      (node (ref "C238") (pin "2") (pinfunction "2_2") (pintype "passive"))
      (node (ref "C239") (pin "2") (pinfunction "2_2") (pintype "passive"))
      (node (ref "C240") (pin "2") (pinfunction "2_2") (pintype "passive"))
      (node (ref "C241") (pin "2") (pinfunction "2_2") (pintype "passive"))
      (node (ref "C242") (pin "2") (pinfunction "2_2") (pintype "passive"))
      (node (ref "C53") (pin "2") (pinfunction "2_2") (pintype "passive"))
      (node (ref "C54") (pin "2") (pinfunction "2_2") (pintype "passive"))
      (node (ref "C55") (pin "2") (pinfunction "2_2") (pintype "passive"))
      (node (ref "C56") (pin "2") (pinfunction "2_2") (pintype "passive"))
      (node (ref "C57") (pin "2") (pinfunction "2_2") (pintype "passive"))
      (node (ref "C58") (pin "2") (pinfunction "2_2") (pintype "passive"))
      (node (ref "C59") (pin "2") (pinfunction "2_2") (pintype "passive"))
      (node (ref "C60") (pin "2") (pinfunction "2_2") (pintype "passive"))
      (node (ref "C61") (pin "2") (pinfunction "2_2") (pintype "passive"))
      (node (ref "C62") (pin "2") (pinfunction "2_2") (pintype "passive"))
      (node (ref "C63") (pin "2") (pinfunction "2_2") (pintype "passive"))
      (node (ref "C64") (pin "2") (pinfunction "2_2") (pintype "passive"))
      (node (ref "C65") (pin "2") (pinfunction "2_2") (pintype "passive"))
      (node (ref "C66") (pin "2") (pinfunction "2_2") (pintype "passive"))
      (node (ref "C67") (pin "2") (pinfunction "2_2") (pintype "passive"))
      (node (ref "C68") (pin "2") (pinfunction "2_2") (pintype "passive"))
      (node (ref "C69") (pin "2") (pinfunction "2_2") (pintype "passive"))
      (node (ref "C70") (pin "2") (pinfunction "2_2") (pintype "passive"))
      (node (ref "C71") (pin "2") (pinfunction "2_2") (pintype "passive"))
      (node (ref "R112") (pin "1") (pinfunction "1_1") (pintype "passive"))
      (node (ref "R123") (pin "1") (pinfunction "1_1") (pintype "passive"))
      (node (ref "R41") (pin "1") (pinfunction "1_1") (pintype "passive"))
      (node (ref "R43") (pin "1") (pinfunction "1_1") (pintype "passive"))
      (node (ref "U25") (pin "3") (pinfunction "GND_3") (pintype "power_in"))
      (node (ref "U5") (pin "13") (pinfunction "VSS_PS_13") (pintype "power_in"))
      (node (ref "U5") (pin "29") (pinfunction "VSS_29") (pintype "power_in"))
      (node (ref "U5") (pin "49") (pinfunction "GND-PAD_49") (pintype "power_in"))
      (node (ref "Y1") (pin "2") (pinfunction "2_2") (pintype "passive"))
      (node (ref "Y1") (pin "4") (pinfunction "4_4") (pintype "passive"))
    )
    (net (code "52") (name "SH_GND") (class "Default")
      (node (ref "J2") (pin "17") (pinfunction "SHLD_17") (pintype "passive"))
      (node (ref "J2") (pin "18") (pinfunction "SHLD_18") (pintype "passive"))
      (node (ref "J2") (pin "19") (pinfunction "SHLD_19") (pintype "passive"))
      (node (ref "J2") (pin "20") (pinfunction "SHLD_20") (pintype "passive"))
      (node (ref "J2") (pin "21") (pinfunction "SHLD_21") (pintype "passive"))
      (node (ref "J2") (pin "22") (pinfunction "SHLD_22") (pintype "passive"))
      (node (ref "R41") (pin "2") (pinfunction "2_2") (pintype "passive"))
    )
  )
)
